# CNC_Power_V2.net
KiCad netlist of a schematic drawn in EAGLE
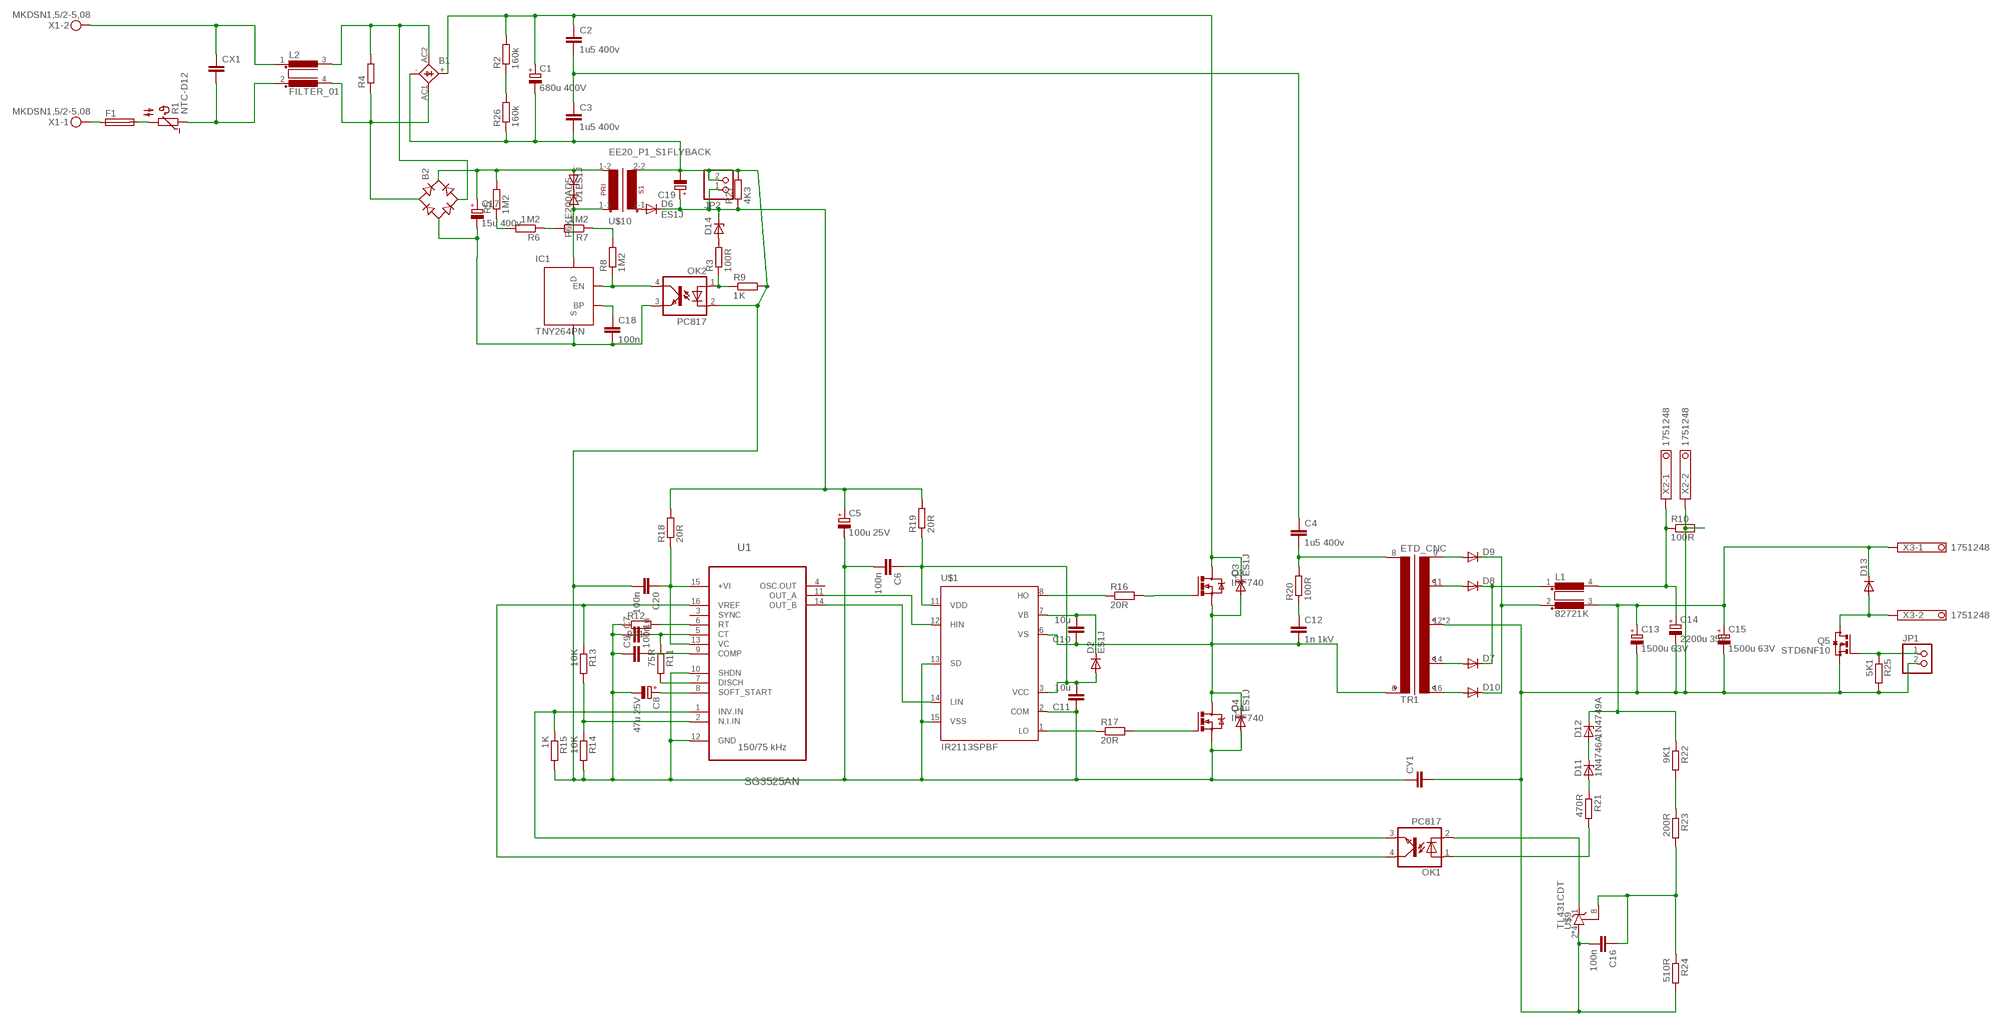
[diagram p0: schematic, sheet 1]

(export (version "E")
  (design (tool "Eeschema 10.0.6"))
  (components
    (comp (ref "B1")
      (value "KBL")
      (footprint "eagle-import:KBL")
      (libsource (lib "eagle-import") (part "KBL"))
    )
    (comp (ref "B2")
      (value "RB1A")
      (footprint "eagle-import:RB1A")
      (libsource (lib "eagle-import") (part "RB1A"))
    )
    (comp (ref "C1")
      (value "680u 400V")
      (footprint "eagle-import:EB35D")
      (libsource (lib "eagle-import") (part "CPOL-EUE10-35"))
    )
    (comp (ref "C2")
      (value "1u5 400v")
      (footprint "eagle-import:C225-074X268")
      (libsource (lib "eagle-import") (part "C-EU225-074X268"))
    )
    (comp (ref "C3")
      (value "1u5 400v")
      (footprint "eagle-import:C225-074X268")
      (libsource (lib "eagle-import") (part "C-EU225-074X268"))
    )
    (comp (ref "C4")
      (value "1u5 400v")
      (footprint "eagle-import:C225-074X268")
      (libsource (lib "eagle-import") (part "C-EU225-074X268"))
    )
    (comp (ref "C5")
      (value "100u 25V")
      (footprint "eagle-import:E2,5-7")
      (libsource (lib "eagle-import") (part "CPOL-EUE2.5-7"))
    )
    (comp (ref "C6")
      (value "100n")
      (footprint "eagle-import:C0805")
      (libsource (lib "eagle-import") (part "C-EUC0805"))
    )
    (comp (ref "C7")
      (value "1n")
      (footprint "eagle-import:C0805")
      (libsource (lib "eagle-import") (part "C-EUC0805"))
    )
    (comp (ref "C8")
      (value "47u 25V")
      (footprint "eagle-import:E2,5-7")
      (libsource (lib "eagle-import") (part "CPOL-EUE2.5-7"))
    )
    (comp (ref "C9")
      (value "100n")
      (footprint "eagle-import:C0805")
      (libsource (lib "eagle-import") (part "C-EUC0805"))
    )
    (comp (ref "C10")
      (value "10u")
      (footprint "eagle-import:C0805")
      (libsource (lib "eagle-import") (part "C-EUC0805"))
    )
    (comp (ref "C11")
      (value "10u")
      (footprint "eagle-import:C0805")
      (libsource (lib "eagle-import") (part "C-EUC0805"))
    )
    (comp (ref "C12")
      (value "1n 1kV")
      (footprint "eagle-import:C050-025X075")
      (libsource (lib "eagle-import") (part "C-EU050-025X075"))
    )
    (comp (ref "C13")
      (value "1500u 63V")
      (footprint "eagle-import:E7,5-18")
      (libsource (lib "eagle-import") (part "CPOL-EUE7.5-18"))
    )
    (comp (ref "C14")
      (value "2200u 35V")
      (footprint "eagle-import:E7,5-18")
      (libsource (lib "eagle-import") (part "CPOL-EUE7.5-18"))
    )
    (comp (ref "C15")
      (value "1500u 63V")
      (footprint "eagle-import:E7,5-18")
      (libsource (lib "eagle-import") (part "CPOL-EUE7.5-18"))
    )
    (comp (ref "C16")
      (value "100n")
      (footprint "eagle-import:C0805")
      (libsource (lib "eagle-import") (part "C-EUC0805"))
    )
    (comp (ref "C17")
      (value "15u 400v")
      (footprint "eagle-import:E5-13")
      (libsource (lib "eagle-import") (part "CPOL-EUE5-13"))
    )
    (comp (ref "C18")
      (value "100n")
      (footprint "eagle-import:C0805")
      (libsource (lib "eagle-import") (part "C-EUC0805"))
    )
    (comp (ref "C19")
      (value "CPOL-EUE2.5-7")
      (footprint "eagle-import:E2,5-7")
      (libsource (lib "eagle-import") (part "CPOL-EUE2.5-7"))
    )
    (comp (ref "C20")
      (value "100n")
      (footprint "eagle-import:C0805")
      (libsource (lib "eagle-import") (part "C-EUC0805"))
    )
    (comp (ref "CX1")
      (value "CXXC15B8")
      (footprint "eagle-import:XC15B8")
      (libsource (lib "eagle-import") (part "CXXC15B8"))
    )
    (comp (ref "CY1")
      (value "CYYC10B4")
      (footprint "eagle-import:YC10B4")
      (libsource (lib "eagle-import") (part "CYYC10B4"))
    )
    (comp (ref "D1")
      (value "P6KE200A")
      (footprint "eagle-import:DO204-10")
      (libsource (lib "eagle-import") (part "DIODE-DO204-10"))
    )
    (comp (ref "D2")
      (value "ES1J")
      (footprint "eagle-import:DO214AC")
      (libsource (lib "eagle-import") (part "DIODE-DO214AC"))
    )
    (comp (ref "D3")
      (value "ES1J")
      (footprint "eagle-import:DO214AC")
      (libsource (lib "eagle-import") (part "DIODE-DO214AC"))
    )
    (comp (ref "D4")
      (value "ES1J")
      (footprint "eagle-import:DO214AC")
      (libsource (lib "eagle-import") (part "DIODE-DO214AC"))
    )
    (comp (ref "D5")
      (value "ES1J")
      (footprint "eagle-import:DO214AC")
      (libsource (lib "eagle-import") (part "DIODE-DO214AC"))
    )
    (comp (ref "D6")
      (value "ES1J")
      (footprint "eagle-import:DO214AC")
      (libsource (lib "eagle-import") (part "DIODE-DO214AC"))
    )
    (comp (ref "D7")
      (value "DIODE-DO220S")
      (footprint "eagle-import:DO220S")
      (libsource (lib "eagle-import") (part "DIODE-DO220S"))
    )
    (comp (ref "D8")
      (value "DIODE-DO220S")
      (footprint "eagle-import:DO220S")
      (libsource (lib "eagle-import") (part "DIODE-DO220S"))
    )
    (comp (ref "D9")
      (value "DIODE-DO220S")
      (footprint "eagle-import:DO220S")
      (libsource (lib "eagle-import") (part "DIODE-DO220S"))
    )
    (comp (ref "D10")
      (value "DIODE-DO220S")
      (footprint "eagle-import:DO220S")
      (libsource (lib "eagle-import") (part "DIODE-DO220S"))
    )
    (comp (ref "D11")
      (value "1N4746A")
      (footprint "eagle-import:DO41Z10")
      (libsource (lib "eagle-import") (part "ZENER-DIODEDO41Z10"))
    )
    (comp (ref "D12")
      (value "1N4749A")
      (footprint "eagle-import:DO41Z10")
      (libsource (lib "eagle-import") (part "ZENER-DIODEDO41Z10"))
    )
    (comp (ref "D13")
      (value "DIODE-DO220S")
      (footprint "eagle-import:DO220S")
      (libsource (lib "eagle-import") (part "DIODE-DO220S"))
    )
    (comp (ref "D14")
      (value "ZENER-DIODEDO41Z10")
      (footprint "eagle-import:DO41Z10")
      (libsource (lib "eagle-import") (part "ZENER-DIODEDO41Z10"))
    )
    (comp (ref "F1")
      (value "SH22,5")
      (footprint "eagle-import:SH22,5")
      (fields (field (name "MF") "SCHURTER") (field (name "MPN") "0031.8201"))
      (libsource (lib "eagle-import") (part "SH22,5"))
    )
    (comp (ref "IC1")
      (value "TNY264PN")
      (footprint "eagle-import:DIP-8B")
      (libsource (lib "eagle-import") (part "TNY264PN"))
    )
    (comp (ref "JP1")
      (value "PINHD-1X2")
      (footprint "eagle-import:1X02")
      (libsource (lib "eagle-import") (part "PINHD-1X2"))
    )
    (comp (ref "JP2")
      (value "PINHD-1X2")
      (footprint "eagle-import:1X02")
      (libsource (lib "eagle-import") (part "PINHD-1X2"))
    )
    (comp (ref "L1")
      (value "82721K")
      (footprint "eagle-import:82721K")
      (libsource (lib "eagle-import") (part "82721K"))
    )
    (comp (ref "L2")
      (value "FILTER_01")
      (footprint "eagle-import:82721K")
      (libsource (lib "eagle-import") (part "FILTER_01"))
    )
    (comp (ref "OK1")
      (value "PC817")
      (footprint "eagle-import:DIL04")
      (fields (field (name "MPN") "PC817X4J000F"))
      (libsource (lib "eagle-import") (part "PC817"))
    )
    (comp (ref "OK2")
      (value "PC817")
      (footprint "eagle-import:DIL04")
      (fields (field (name "MPN") "PC817X4J000F"))
      (libsource (lib "eagle-import") (part "PC817"))
    )
    (comp (ref "Q3")
      (value "IRF740")
      (footprint "eagle-import:TO220BV")
      (libsource (lib "eagle-import") (part "IRF740"))
    )
    (comp (ref "Q4")
      (value "IRF740")
      (footprint "eagle-import:TO220BV")
      (libsource (lib "eagle-import") (part "IRF740"))
    )
    (comp (ref "Q5")
      (value "STD6NF10")
      (footprint "eagle-import:DPAK")
      (libsource (lib "eagle-import") (part "STD6NF10"))
    )
    (comp (ref "R1")
      (value "NTC-D12")
      (footprint "eagle-import:NTC-D12")
      (libsource (lib "eagle-import") (part "NTC-D12"))
    )
    (comp (ref "R2")
      (value "160k")
      (footprint "eagle-import:0207_10")
      (libsource (lib "eagle-import") (part "R-EU_0207/10"))
    )
    (comp (ref "R3")
      (value "100R")
      (footprint "eagle-import:R0805")
      (libsource (lib "eagle-import") (part "R-EU_R0805"))
    )
    (comp (ref "R4")
      (value "R-EU_0309/10")
      (footprint "eagle-import:0309_10")
      (libsource (lib "eagle-import") (part "R-EU_0309/10"))
    )
    (comp (ref "R5")
      (value "1M2")
      (footprint "eagle-import:R0805")
      (libsource (lib "eagle-import") (part "R-EU_R0805"))
    )
    (comp (ref "R6")
      (value "1M2")
      (footprint "eagle-import:R0805")
      (libsource (lib "eagle-import") (part "R-EU_R0805"))
    )
    (comp (ref "R7")
      (value "1M2")
      (footprint "eagle-import:R0805")
      (libsource (lib "eagle-import") (part "R-EU_R0805"))
    )
    (comp (ref "R8")
      (value "1M2")
      (footprint "eagle-import:R0805")
      (libsource (lib "eagle-import") (part "R-EU_R0805"))
    )
    (comp (ref "R9")
      (value "1K")
      (footprint "eagle-import:R0805")
      (libsource (lib "eagle-import") (part "R-EU_R0805"))
    )
    (comp (ref "R10")
      (value "100R")
      (footprint "eagle-import:SQP-5")
      (libsource (lib "eagle-import") (part "R_SQP-5"))
    )
    (comp (ref "R11")
      (value "75R")
      (footprint "eagle-import:R0805")
      (libsource (lib "eagle-import") (part "R-EU_R0805"))
    )
    (comp (ref "R12")
      (value "9K1")
      (footprint "eagle-import:R0805")
      (libsource (lib "eagle-import") (part "R-EU_R0805"))
    )
    (comp (ref "R13")
      (value "10K")
      (footprint "eagle-import:R0805")
      (libsource (lib "eagle-import") (part "R-EU_R0805"))
    )
    (comp (ref "R14")
      (value "10K")
      (footprint "eagle-import:R0805")
      (libsource (lib "eagle-import") (part "R-EU_R0805"))
    )
    (comp (ref "R15")
      (value "1K")
      (footprint "eagle-import:R0805")
      (libsource (lib "eagle-import") (part "R-EU_R0805"))
    )
    (comp (ref "R16")
      (value "20R")
      (footprint "eagle-import:0309_12")
      (libsource (lib "eagle-import") (part "R-EU_0309/12"))
    )
    (comp (ref "R17")
      (value "20R")
      (footprint "eagle-import:0309_12")
      (libsource (lib "eagle-import") (part "R-EU_0309/12"))
    )
    (comp (ref "R18")
      (value "20R")
      (footprint "eagle-import:R2512")
      (libsource (lib "eagle-import") (part "R-EU_R2512"))
    )
    (comp (ref "R19")
      (value "20R")
      (footprint "eagle-import:R2512")
      (libsource (lib "eagle-import") (part "R-EU_R2512"))
    )
    (comp (ref "R20")
      (value "100R")
      (footprint "eagle-import:0617_17")
      (libsource (lib "eagle-import") (part "R-EU_0617/17"))
    )
    (comp (ref "R21")
      (value "470R")
      (footprint "eagle-import:R0805")
      (libsource (lib "eagle-import") (part "R-EU_R0805"))
    )
    (comp (ref "R22")
      (value "9K1")
      (footprint "eagle-import:R0805")
      (libsource (lib "eagle-import") (part "R-EU_R0805"))
    )
    (comp (ref "R23")
      (value "200R")
      (footprint "eagle-import:R0805")
      (libsource (lib "eagle-import") (part "R-EU_R0805"))
    )
    (comp (ref "R24")
      (value "510R")
      (footprint "eagle-import:R0805")
      (libsource (lib "eagle-import") (part "R-EU_R0805"))
    )
    (comp (ref "R25")
      (value "5K1")
      (footprint "eagle-import:R0805")
      (libsource (lib "eagle-import") (part "R-EU_R0805"))
    )
    (comp (ref "R26")
      (value "160k")
      (footprint "eagle-import:0207_10")
      (libsource (lib "eagle-import") (part "R-EU_0207/10"))
    )
    (comp (ref "R27")
      (value "4K3")
      (footprint "eagle-import:R0805")
      (libsource (lib "eagle-import") (part "R-EU_R0805"))
    )
    (comp (ref "TR1")
      (value "ETD_CNC")
      (footprint "eagle-import:ETD39_16PIN")
      (libsource (lib "eagle-import") (part "ETD_CNC"))
    )
    (comp (ref "U$1")
      (value "IR2113SPBF")
      (footprint "eagle-import:SO16W")
      (libsource (lib "eagle-import") (part "IR2113SPBF"))
    )
    (comp (ref "U$9")
      (value "TL431CDT")
      (footprint "eagle-import:SO8")
      (libsource (lib "eagle-import") (part "TL431CDT"))
    )
    (comp (ref "U$10")
      (value "EE20_P1_S1FLYBACK")
      (footprint "eagle-import:EE20_P1_S1-REV-4PIN")
      (libsource (lib "eagle-import") (part "EE20_P1_S1FLYBACK"))
    )
    (comp (ref "U1")
      (value "SG3525AN")
      (footprint "eagle-import:DIP254P762X510-16")
      (libsource (lib "eagle-import") (part "SG3525AN"))
    )
    (comp (ref "X1")
      (value "MKDSN1,5/2-5,08")
      (footprint "eagle-import:MKDSN1,5_2-5,08")
      (libsource (lib "eagle-import") (part "MKDSN1,5/2-5,08"))
    )
    (comp (ref "X2")
      (value "1751248")
      (footprint "eagle-import:1751248")
      (libsource (lib "eagle-import") (part "1751248"))
    )
    (comp (ref "X3")
      (value "1751248")
      (footprint "eagle-import:1751248")
      (libsource (lib "eagle-import") (part "1751248"))
    )
  )
  (nets
    (net (code "1") (name "Net-(B1-AC1)") (class "Default")
      (node (ref "B1") (pin "AC2") (pinfunction "AC1_AC2") (pintype "passive"))
      (node (ref "B2") (pin "AC2") (pinfunction "AC2_AC2") (pintype "passive"))
      (node (ref "L2") (pin "3") (pinfunction "2_3") (pintype "passive"))
      (node (ref "R4") (pin "2") (pinfunction "2_2") (pintype "passive"))
    )
    (net (code "2") (name "Net-(B1-AC2)") (class "Default")
      (node (ref "B1") (pin "AC1") (pinfunction "AC2_AC1") (pintype "passive"))
      (node (ref "B2") (pin "AC1") (pinfunction "AC1_AC1") (pintype "passive"))
      (node (ref "L2") (pin "4") (pinfunction "4_4") (pintype "passive"))
      (node (ref "R4") (pin "1") (pinfunction "1_1") (pintype "passive"))
    )
    (net (code "3") (name "Net-(B1-Pad+)") (class "Default")
      (node (ref "B1") (pin "+") (pinfunction "+_+") (pintype "passive"))
      (node (ref "C1") (pin "+") (pinfunction "+_+") (pintype "passive"))
      (node (ref "C2") (pin "1") (pinfunction "1_1") (pintype "passive"))
      (node (ref "D3") (pin "C") (pinfunction "C_C") (pintype "passive"))
      (node (ref "Q3") (pin "D") (pinfunction "D_D") (pintype "passive"))
      (node (ref "R2") (pin "2") (pinfunction "2_2") (pintype "passive"))
    )
    (net (code "4") (name "Net-(C2-Pad2)") (class "Default")
      (node (ref "C2") (pin "2") (pinfunction "2_2") (pintype "passive"))
      (node (ref "C3") (pin "1") (pinfunction "1_1") (pintype "passive"))
      (node (ref "C4") (pin "1") (pinfunction "1_1") (pintype "passive"))
    )
    (net (code "5") (name "Net-(C12-Pad1)") (class "Default")
      (node (ref "C12") (pin "1") (pinfunction "1_1") (pintype "passive"))
      (node (ref "R20") (pin "1") (pinfunction "1_1") (pintype "passive"))
    )
    (net (code "6") (name "Net-(C19-Pad+)") (class "Default")
      (node (ref "C19") (pin "+") (pinfunction "+_+") (pintype "passive"))
      (node (ref "C5") (pin "+") (pinfunction "+_+") (pintype "passive"))
      (node (ref "D14") (pin "C") (pinfunction "C_C") (pintype "passive"))
      (node (ref "D6") (pin "C") (pinfunction "C_C") (pintype "passive"))
      (node (ref "JP2") (pin "1") (pinfunction "1_1") (pintype "passive"))
      (node (ref "R18") (pin "2") (pinfunction "2_2") (pintype "passive"))
      (node (ref "R19") (pin "2") (pinfunction "2_2") (pintype "passive"))
      (node (ref "R27") (pin "1") (pinfunction "1_1") (pintype "passive"))
    )
    (net (code "7") (name "Net-(D1-PadC)") (class "Default")
      (node (ref "D1") (pin "C") (pinfunction "C_C") (pintype "passive"))
      (node (ref "D5") (pin "C") (pinfunction "C_C") (pintype "passive"))
    )
    (net (code "8") (name "Net-(D7-PadC)") (class "Default")
      (node (ref "D7") (pin "C") (pinfunction "C_C") (pintype "passive"))
      (node (ref "D8") (pin "C") (pinfunction "C_C") (pintype "passive"))
      (node (ref "L1") (pin "1") (pinfunction "1_1") (pintype "passive"))
    )
    (net (code "9") (name "Net-(D11-PadA)") (class "Default")
      (node (ref "D11") (pin "A") (pinfunction "A_A") (pintype "passive"))
      (node (ref "R21") (pin "1") (pinfunction "1_1") (pintype "passive"))
    )
    (net (code "10") (name "Net-(D11-PadC)") (class "Default")
      (node (ref "D11") (pin "C") (pinfunction "C_C") (pintype "passive"))
      (node (ref "D12") (pin "A") (pinfunction "A_A") (pintype "passive"))
    )
    (net (code "11") (name "Net-(D14-PadA)") (class "Default")
      (node (ref "D14") (pin "A") (pinfunction "A_A") (pintype "passive"))
      (node (ref "R3") (pin "2") (pinfunction "2_2") (pintype "passive"))
    )
    (net (code "12") (name "Net-(F1-Pad2)") (class "Default")
      (node (ref "F1") (pin "2") (pinfunction "2_2") (pintype "passive"))
      (node (ref "R1") (pin "2") (pinfunction "2_2") (pintype "passive"))
    )
    (net (code "13") (name "Net-(IC1-BP)") (class "Default")
      (node (ref "C18") (pin "1") (pinfunction "1_1") (pintype "passive"))
      (node (ref "IC1") (pin "1") (pinfunction "BP_1") (pintype "input"))
    )
    (net (code "14") (name "Net-(IC1-D)") (class "Default")
      (node (ref "D5") (pin "A") (pinfunction "A_A") (pintype "passive"))
      (node (ref "IC1") (pin "5") (pinfunction "D_5") (pintype "input"))
      (node (ref "U$10") (pin "1-1") (pinfunction "P1-1_1-1") (pintype "passive"))
    )
    (net (code "15") (name "Net-(IC1-EN)") (class "Default")
      (node (ref "IC1") (pin "4") (pinfunction "EN_4") (pintype "input"))
      (node (ref "OK2") (pin "4") (pinfunction "COL_4") (pintype "passive"))
      (node (ref "R8") (pin "1") (pinfunction "1_1") (pintype "passive"))
    )
    (net (code "16") (name "Net-(JP1-Pad1)") (class "Default")
      (node (ref "JP1") (pin "1") (pinfunction "1_1") (pintype "passive"))
      (node (ref "Q5") (pin "G") (pinfunction "G_G") (pintype "passive"))
      (node (ref "R25") (pin "1") (pinfunction "1_1") (pintype "passive"))
    )
    (net (code "17") (name "Net-(L1-2)") (class "Default")
      (node (ref "C14") (pin "+") (pinfunction "+_+") (pintype "passive"))
      (node (ref "L1") (pin "4") (pinfunction "2_4") (pintype "passive"))
      (node (ref "R10") (pin "1") (pinfunction "1_1") (pintype "passive"))
      (node (ref "X2") (pin "1") (pinfunction "K_1") (pintype "passive"))
    )
    (net (code "18") (name "Net-(L1-3)") (class "Default")
      (node (ref "D10") (pin "C") (pinfunction "C_C") (pintype "passive"))
      (node (ref "D9") (pin "C") (pinfunction "C_C") (pintype "passive"))
      (node (ref "L1") (pin "2") (pinfunction "3_2") (pintype "passive"))
    )
    (net (code "19") (name "Net-(L1-4)") (class "Default")
      (node (ref "C13") (pin "+") (pinfunction "+_+") (pintype "passive"))
      (node (ref "C15") (pin "+") (pinfunction "+_+") (pintype "passive"))
      (node (ref "D12") (pin "C") (pinfunction "C_C") (pintype "passive"))
      (node (ref "D13") (pin "C") (pinfunction "C_C") (pintype "passive"))
      (node (ref "L1") (pin "3") (pinfunction "4_3") (pintype "passive"))
      (node (ref "R22") (pin "1") (pinfunction "1_1") (pintype "passive"))
      (node (ref "X3") (pin "1") (pinfunction "K_1") (pintype "passive"))
    )
    (net (code "20") (name "Net-(L2-3)") (class "Default")
      (node (ref "CX1") (pin "2") (pinfunction "2_2") (pintype "passive"))
      (node (ref "L2") (pin "2") (pinfunction "3_2") (pintype "passive"))
      (node (ref "R1") (pin "1") (pinfunction "1_1") (pintype "passive"))
    )
    (net (code "21") (name "Net-(OK1-A)") (class "Default")
      (node (ref "OK1") (pin "1") (pinfunction "A_1") (pintype "passive"))
      (node (ref "R21") (pin "2") (pinfunction "2_2") (pintype "passive"))
    )
    (net (code "22") (name "Net-(OK1-C)") (class "Default")
      (node (ref "OK1") (pin "2") (pinfunction "C_2") (pintype "passive"))
      (node (ref "U$9") (pin "1") (pinfunction "C_1") (pintype "passive"))
    )
    (net (code "23") (name "Net-(OK1-COL)") (class "Default")
      (node (ref "OK1") (pin "4") (pinfunction "COL_4") (pintype "passive"))
      (node (ref "R13") (pin "1") (pinfunction "1_1") (pintype "passive"))
      (node (ref "U1") (pin "16") (pinfunction "VREF_16") (pintype "passive"))
    )
    (net (code "24") (name "Net-(OK1-EMIT)") (class "Default")
      (node (ref "OK1") (pin "3") (pinfunction "EMIT_3") (pintype "passive"))
      (node (ref "R15") (pin "1") (pinfunction "1_1") (pintype "passive"))
      (node (ref "U1") (pin "1") (pinfunction "INV.IN_1") (pintype "input"))
    )
    (net (code "25") (name "Net-(OK2-A)") (class "Default")
      (node (ref "OK2") (pin "1") (pinfunction "A_1") (pintype "passive"))
      (node (ref "R3") (pin "1") (pinfunction "1_1") (pintype "passive"))
      (node (ref "R9") (pin "1") (pinfunction "1_1") (pintype "passive"))
    )
    (net (code "26") (name "Net-(OK2-C)") (class "Default")
      (node (ref "B1") (pin "-") (pinfunction "-_-") (pintype "passive"))
      (node (ref "C1") (pin "-") (pinfunction "-_-") (pintype "passive"))
      (node (ref "C11") (pin "1") (pinfunction "1_1") (pintype "passive"))
      (node (ref "C19") (pin "-") (pinfunction "-_-") (pintype "passive"))
      (node (ref "C20") (pin "2") (pinfunction "2_2") (pintype "passive"))
      (node (ref "C3") (pin "2") (pinfunction "2_2") (pintype "passive"))
      (node (ref "C5") (pin "-") (pinfunction "-_-") (pintype "passive"))
      (node (ref "C6") (pin "2") (pinfunction "2_2") (pintype "passive"))
      (node (ref "C7") (pin "1") (pinfunction "1_1") (pintype "passive"))
      (node (ref "C8") (pin "-") (pinfunction "-_-") (pintype "passive"))
      (node (ref "C9") (pin "1") (pinfunction "1_1") (pintype "passive"))
      (node (ref "CY1") (pin "1") (pinfunction "1_1") (pintype "passive"))
      (node (ref "D4") (pin "A") (pinfunction "A_A") (pintype "passive"))
      (node (ref "JP2") (pin "2") (pinfunction "2_2") (pintype "passive"))
      (node (ref "OK2") (pin "2") (pinfunction "C_2") (pintype "passive"))
      (node (ref "Q4") (pin "S") (pinfunction "S_S") (pintype "passive"))
      (node (ref "R12") (pin "1") (pinfunction "1_1") (pintype "passive"))
      (node (ref "R14") (pin "2") (pinfunction "2_2") (pintype "passive"))
      (node (ref "R15") (pin "2") (pinfunction "2_2") (pintype "passive"))
      (node (ref "R26") (pin "1") (pinfunction "1_1") (pintype "passive"))
      (node (ref "R27") (pin "2") (pinfunction "2_2") (pintype "passive"))
      (node (ref "R9") (pin "2") (pinfunction "2_2") (pintype "passive"))
      (node (ref "U$1") (pin "13") (pinfunction "SD_13") (pintype "input"))
      (node (ref "U$1") (pin "15") (pinfunction "VSS_15") (pintype "power_in"))
      (node (ref "U$1") (pin "2") (pinfunction "COM_2") (pintype "power_in"))
      (node (ref "U$10") (pin "2-2") (pinfunction "S1-2_2-2") (pintype "passive"))
      (node (ref "U1") (pin "10") (pinfunction "SHDN_10") (pintype "input"))
      (node (ref "U1") (pin "12") (pinfunction "GND_12") (pintype "passive"))
    )
    (net (code "27") (name "Net-(OK2-EMIT)") (class "Default")
      (node (ref "B2") (pin "-") (pinfunction "-_-") (pintype "passive"))
      (node (ref "C17") (pin "-") (pinfunction "-_-") (pintype "passive"))
      (node (ref "C18") (pin "2") (pinfunction "2_2") (pintype "passive"))
      (node (ref "IC1") (pin "2") (pinfunction "S_2") (pintype "input"))
      (node (ref "IC1") (pin "3") (pinfunction "S_3") (pintype "input"))
      (node (ref "IC1") (pin "7") (pinfunction "S_7") (pintype "input"))
      (node (ref "IC1") (pin "8") (pinfunction "S_8") (pintype "input"))
      (node (ref "OK2") (pin "3") (pinfunction "EMIT_3") (pintype "passive"))
    )
    (net (code "28") (name "Net-(Q3-PadG)") (class "Default")
      (node (ref "Q3") (pin "G") (pinfunction "G_G") (pintype "passive"))
      (node (ref "R16") (pin "2") (pinfunction "2_2") (pintype "passive"))
    )
    (net (code "29") (name "Net-(Q4-PadG)") (class "Default")
      (node (ref "Q4") (pin "G") (pinfunction "G_G") (pintype "passive"))
      (node (ref "R17") (pin "2") (pinfunction "2_2") (pintype "passive"))
    )
    (net (code "30") (name "Net-(R2-Pad1)") (class "Default")
      (node (ref "R2") (pin "1") (pinfunction "1_1") (pintype "passive"))
      (node (ref "R26") (pin "2") (pinfunction "2_2") (pintype "passive"))
    )
    (net (code "31") (name "Net-(R5-Pad1)") (class "Default")
      (node (ref "R5") (pin "1") (pinfunction "1_1") (pintype "passive"))
      (node (ref "R6") (pin "2") (pinfunction "2_2") (pintype "passive"))
    )
    (net (code "32") (name "Net-(R6-Pad1)") (class "Default")
      (node (ref "R6") (pin "1") (pinfunction "1_1") (pintype "passive"))
      (node (ref "R7") (pin "2") (pinfunction "2_2") (pintype "passive"))
    )
    (net (code "33") (name "Net-(R7-Pad1)") (class "Default")
      (node (ref "R7") (pin "1") (pinfunction "1_1") (pintype "passive"))
      (node (ref "R8") (pin "2") (pinfunction "2_2") (pintype "passive"))
    )
    (net (code "34") (name "Net-(R22-Pad2)") (class "Default")
      (node (ref "R22") (pin "2") (pinfunction "2_2") (pintype "passive"))
      (node (ref "R23") (pin "1") (pinfunction "1_1") (pintype "passive"))
    )
    (net (code "35") (name "Net-(TR1-P1-1)") (class "Default")
      (node (ref "C10") (pin "1") (pinfunction "1_1") (pintype "passive"))
      (node (ref "C12") (pin "2") (pinfunction "2_2") (pintype "passive"))
      (node (ref "D3") (pin "A") (pinfunction "A_A") (pintype "passive"))
      (node (ref "D4") (pin "C") (pinfunction "C_C") (pintype "passive"))
      (node (ref "Q3") (pin "S") (pinfunction "S_S") (pintype "passive"))
      (node (ref "Q4") (pin "D") (pinfunction "D_D") (pintype "passive"))
      (node (ref "TR1") (pin "6") (pinfunction "P1-1_6") (pintype "passive"))
      (node (ref "U$1") (pin "6") (pinfunction "VS_6") (pintype "power_in"))
    )
    (net (code "36") (name "Net-(TR1-P1-2)") (class "Default")
      (node (ref "C4") (pin "2") (pinfunction "2_2") (pintype "passive"))
      (node (ref "R20") (pin "2") (pinfunction "2_2") (pintype "passive"))
      (node (ref "TR1") (pin "8") (pinfunction "P1-2_8") (pintype "passive"))
    )
    (net (code "37") (name "Net-(TR1-S1-1)") (class "Default")
      (node (ref "D10") (pin "A") (pinfunction "A_A") (pintype "passive"))
      (node (ref "TR1") (pin "16") (pinfunction "S1-1_16") (pintype "passive"))
    )
    (net (code "38") (name "Net-(TR1-S1-2)") (class "Default")
      (node (ref "D9") (pin "A") (pinfunction "A_A") (pintype "passive"))
      (node (ref "TR1") (pin "9") (pinfunction "S1-2_9") (pintype "passive"))
    )
    (net (code "39") (name "Net-(TR1-S2-1)") (class "Default")
      (node (ref "D7") (pin "A") (pinfunction "A_A") (pintype "passive"))
      (node (ref "TR1") (pin "14") (pinfunction "S2-1_14") (pintype "passive"))
    )
    (net (code "40") (name "Net-(TR1-S2-2)") (class "Default")
      (node (ref "D8") (pin "A") (pinfunction "A_A") (pintype "passive"))
      (node (ref "TR1") (pin "11") (pinfunction "S2-2_11") (pintype "passive"))
    )
    (net (code "41") (name "Net-(U$1-HIN)") (class "Default")
      (node (ref "U$1") (pin "12") (pinfunction "HIN_12") (pintype "input"))
      (node (ref "U1") (pin "11") (pinfunction "OUT_A_11") (pintype "output"))
    )
    (net (code "42") (name "Net-(U$1-HO)") (class "Default")
      (node (ref "R16") (pin "1") (pinfunction "1_1") (pintype "passive"))
      (node (ref "U$1") (pin "8") (pinfunction "HO_8") (pintype "output"))
    )
    (net (code "43") (name "Net-(U$1-LIN)") (class "Default")
      (node (ref "U$1") (pin "14") (pinfunction "LIN_14") (pintype "input"))
      (node (ref "U1") (pin "14") (pinfunction "OUT_B_14") (pintype "output"))
    )
    (net (code "44") (name "Net-(U$1-LO)") (class "Default")
      (node (ref "R17") (pin "1") (pinfunction "1_1") (pintype "passive"))
      (node (ref "U$1") (pin "1") (pinfunction "LO_1") (pintype "output"))
    )
    (net (code "45") (name "Net-(U$1-VB)") (class "Default")
      (node (ref "C10") (pin "2") (pinfunction "2_2") (pintype "passive"))
      (node (ref "D2") (pin "C") (pinfunction "C_C") (pintype "passive"))
      (node (ref "U$1") (pin "7") (pinfunction "VB_7") (pintype "power_in"))
    )
    (net (code "46") (name "Net-(U$1-VCC)") (class "Default")
      (node (ref "C11") (pin "2") (pinfunction "2_2") (pintype "passive"))
      (node (ref "C6") (pin "1") (pinfunction "1_1") (pintype "passive"))
      (node (ref "D2") (pin "A") (pinfunction "A_A") (pintype "passive"))
      (node (ref "R19") (pin "1") (pinfunction "1_1") (pintype "passive"))
      (node (ref "U$1") (pin "11") (pinfunction "VDD_11") (pintype "power_in"))
      (node (ref "U$1") (pin "3") (pinfunction "VCC_3") (pintype "power_in"))
    )
    (net (code "47") (name "Net-(U$9-R)") (class "Default")
      (node (ref "C16") (pin "1") (pinfunction "1_1") (pintype "passive"))
      (node (ref "R23") (pin "2") (pinfunction "2_2") (pintype "passive"))
      (node (ref "R24") (pin "1") (pinfunction "1_1") (pintype "passive"))
      (node (ref "U$9") (pin "8") (pinfunction "R_8") (pintype "passive"))
    )
    (net (code "48") (name "Net-(U$10-P1-2)") (class "Default")
      (node (ref "B2") (pin "+") (pinfunction "+_+") (pintype "passive"))
      (node (ref "C17") (pin "+") (pinfunction "+_+") (pintype "passive"))
      (node (ref "D1") (pin "A") (pinfunction "A_A") (pintype "passive"))
      (node (ref "R5") (pin "2") (pinfunction "2_2") (pintype "passive"))
      (node (ref "U$10") (pin "1-2") (pinfunction "P1-2_1-2") (pintype "passive"))
    )
    (net (code "49") (name "Net-(U$10-S1-1)") (class "Default")
      (node (ref "D6") (pin "A") (pinfunction "A_A") (pintype "passive"))
      (node (ref "U$10") (pin "2-1") (pinfunction "S1-1_2-1") (pintype "passive"))
    )
    (net (code "50") (name "Net-(U1-+VI)") (class "Default")
      (node (ref "C20") (pin "1") (pinfunction "1_1") (pintype "passive"))
      (node (ref "R18") (pin "1") (pinfunction "1_1") (pintype "passive"))
      (node (ref "U1") (pin "13") (pinfunction "VC_13") (pintype "passive"))
      (node (ref "U1") (pin "15") (pinfunction "+VI_15") (pintype "power_in"))
    )
    (net (code "51") (name "Net-(U1-COMP)") (class "Default")
      (node (ref "C9") (pin "2") (pinfunction "2_2") (pintype "passive"))
      (node (ref "U1") (pin "9") (pinfunction "COMP_9") (pintype "passive"))
    )
    (net (code "52") (name "Net-(U1-CT)") (class "Default")
      (node (ref "C7") (pin "2") (pinfunction "2_2") (pintype "passive"))
      (node (ref "R11") (pin "1") (pinfunction "1_1") (pintype "passive"))
      (node (ref "U1") (pin "5") (pinfunction "CT_5") (pintype "passive"))
    )
    (net (code "53") (name "Net-(U1-DISCH)") (class "Default")
      (node (ref "R11") (pin "2") (pinfunction "2_2") (pintype "passive"))
      (node (ref "U1") (pin "7") (pinfunction "DISCH_7") (pintype "passive"))
    )
    (net (code "54") (name "Net-(U1-N.I.IN)") (class "Default")
      (node (ref "R13") (pin "2") (pinfunction "2_2") (pintype "passive"))
      (node (ref "R14") (pin "1") (pinfunction "1_1") (pintype "passive"))
      (node (ref "U1") (pin "2") (pinfunction "N.I.IN_2") (pintype "input"))
    )
    (net (code "55") (name "Net-(U1-RT)") (class "Default")
      (node (ref "R12") (pin "2") (pinfunction "2_2") (pintype "passive"))
      (node (ref "U1") (pin "6") (pinfunction "RT_6") (pintype "passive"))
    )
    (net (code "56") (name "Net-(U1-SOFT_START)") (class "Default")
      (node (ref "C8") (pin "+") (pinfunction "+_+") (pintype "passive"))
      (node (ref "U1") (pin "8") (pinfunction "SOFT_START_8") (pintype "passive"))
    )
    (net (code "57") (name "Net-(X1A-KL)") (class "Default")
      (node (ref "F1") (pin "1") (pinfunction "1_1") (pintype "passive"))
      (node (ref "X1") (pin "1") (pinfunction "KL_1") (pintype "passive"))
    )
    (net (code "58") (name "Net-(X1B-KL)") (class "Default")
      (node (ref "CX1") (pin "1") (pinfunction "1_1") (pintype "passive"))
      (node (ref "L2") (pin "1") (pinfunction "1_1") (pintype "passive"))
      (node (ref "X1") (pin "2") (pinfunction "KL_2") (pintype "passive"))
    )
    (net (code "59") (name "Net-(X2B-K)") (class "Default")
      (node (ref "C13") (pin "-") (pinfunction "-_-") (pintype "passive"))
      (node (ref "C14") (pin "-") (pinfunction "-_-") (pintype "passive"))
      (node (ref "C15") (pin "-") (pinfunction "-_-") (pintype "passive"))
      (node (ref "C16") (pin "2") (pinfunction "2_2") (pintype "passive"))
      (node (ref "CY1") (pin "2") (pinfunction "2_2") (pintype "passive"))
      (node (ref "JP1") (pin "2") (pinfunction "2_2") (pintype "passive"))
      (node (ref "Q5") (pin "S") (pinfunction "S_S") (pintype "passive"))
      (node (ref "R10") (pin "2") (pinfunction "2_2") (pintype "passive"))
      (node (ref "R24") (pin "2") (pinfunction "2_2") (pintype "passive"))
      (node (ref "R25") (pin "2") (pinfunction "2_2") (pintype "passive"))
      (node (ref "TR1") (pin "12") (pinfunction "S0_12") (pintype "passive"))
      (node (ref "TR1") (pin "13") (pinfunction "S0_13") (pintype "passive"))
      (node (ref "U$9") (pin "2") (pinfunction "A_2") (pintype "passive"))
      (node (ref "U$9") (pin "3") (pinfunction "A_3") (pintype "passive"))
      (node (ref "U$9") (pin "6") (pinfunction "A_6") (pintype "passive"))
      (node (ref "U$9") (pin "7") (pinfunction "A_7") (pintype "passive"))
      (node (ref "X2") (pin "2") (pinfunction "K_2") (pintype "passive"))
    )
    (net (code "60") (name "Net-(X3B-K)") (class "Default")
      (node (ref "D13") (pin "A") (pinfunction "A_A") (pintype "passive"))
      (node (ref "Q5") (pin "D") (pinfunction "D_D") (pintype "passive"))
      (node (ref "X3") (pin "2") (pinfunction "K_2") (pintype "passive"))
    )
    (net (code "61") (name "unconnected-(U1-OSC.OUT-Pad4)") (class "Default")
      (node (ref "U1") (pin "4") (pinfunction "OSC.OUT_4") (pintype "output"))
    )
    (net (code "62") (name "unconnected-(U1-SYNC-Pad3)") (class "Default")
      (node (ref "U1") (pin "3") (pinfunction "SYNC_3") (pintype "passive"))
    )
  )
)
